# bits2.net
KiCad netlist of a schematic drawn in EAGLE
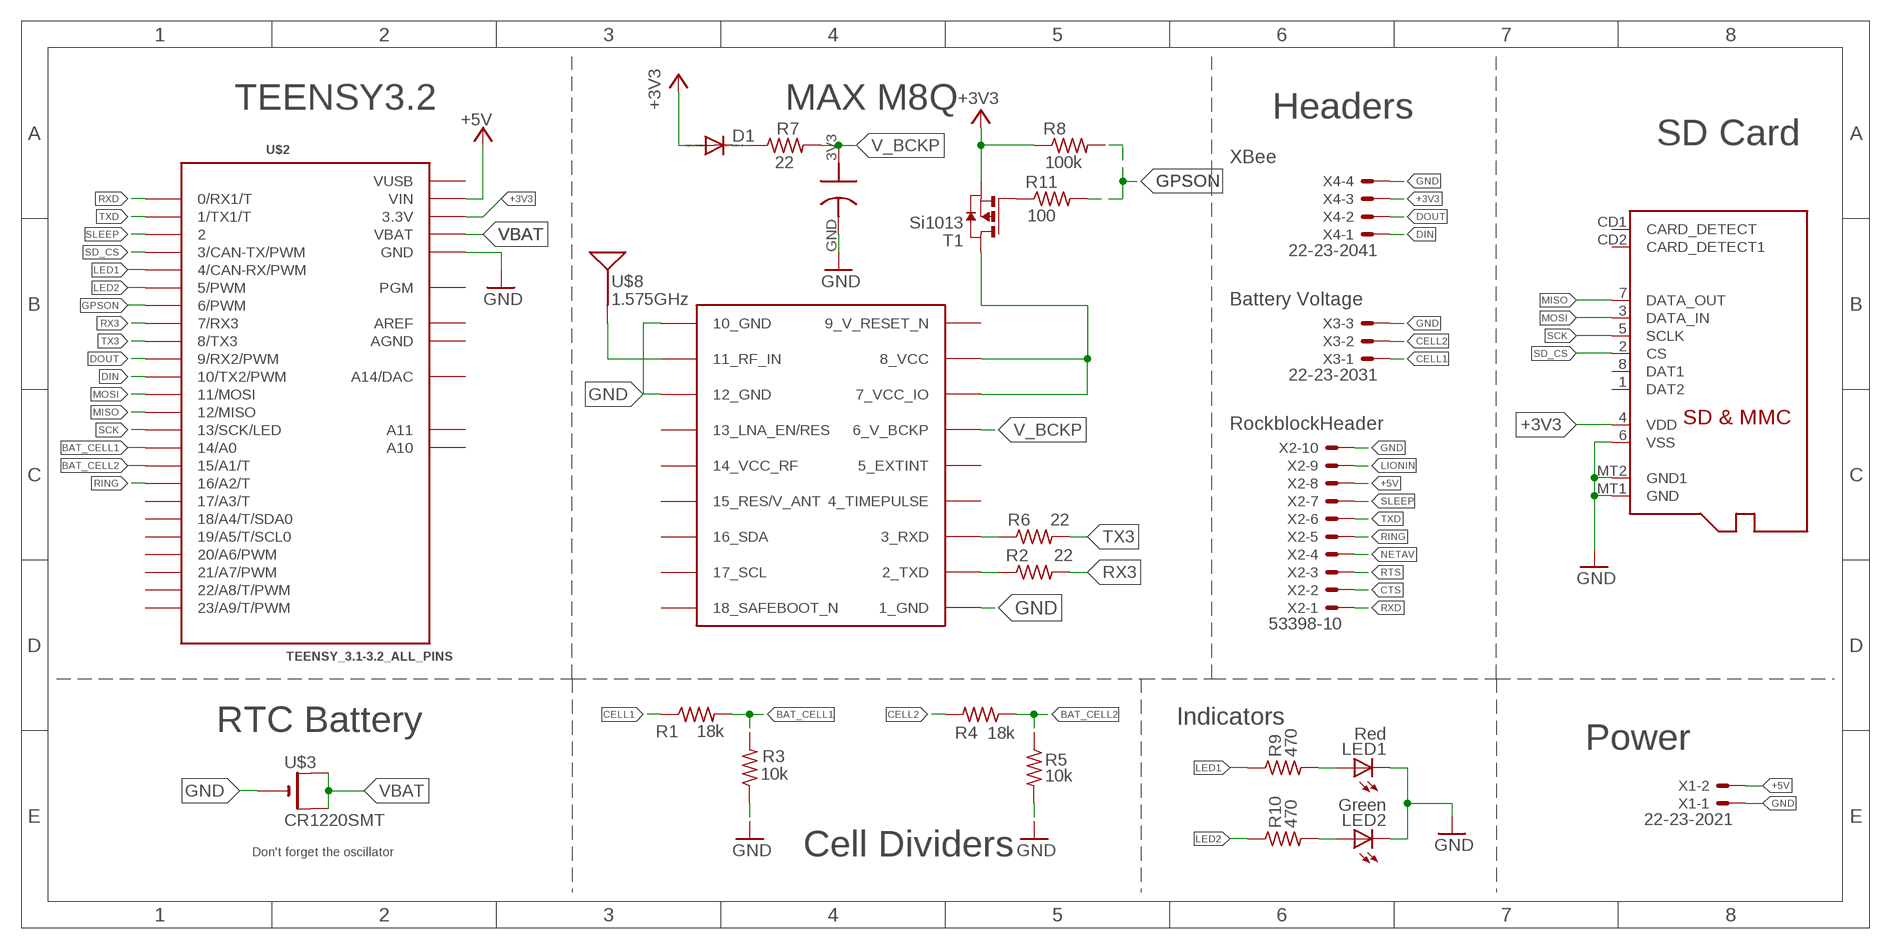
[diagram p0: schematic, sheet 1]

(export (version "E")
  (design (tool "Eeschema 10.0.6"))
  (components
    (comp (ref "C1")
      (value "DCK-3R3E204T614-E")
      (footprint "eagle-import:ELNASUPERCAP")
      (libsource (lib "eagle-import") (part "DCK-3R3E204T614-E"))
    )
    (comp (ref "D1")
      (value "DIODE-SOD523")
      (footprint "eagle-import:SOD523")
      (libsource (lib "eagle-import") (part "DIODE-SOD523"))
    )
    (comp (ref "LED1")
      (value "Red")
      (footprint "eagle-import:CHIP-LED0603")
      (libsource (lib "eagle-import") (part "LEDCHIP-LED0603"))
    )
    (comp (ref "LED2")
      (value "Green")
      (footprint "eagle-import:CHIP-LED0603")
      (libsource (lib "eagle-import") (part "LEDCHIP-LED0603"))
    )
    (comp (ref "R1")
      (value "18k")
      (footprint "eagle-import:R0603")
      (libsource (lib "eagle-import") (part "resistor_348_R-US_R0603"))
    )
    (comp (ref "R2")
      (value "22")
      (footprint "eagle-import:R0603")
      (libsource (lib "eagle-import") (part "R-US_R0603"))
    )
    (comp (ref "R3")
      (value "10k")
      (footprint "eagle-import:R0603")
      (libsource (lib "eagle-import") (part "resistor_348_R-US_R0603"))
    )
    (comp (ref "R4")
      (value "18k")
      (footprint "eagle-import:R0603")
      (libsource (lib "eagle-import") (part "resistor_348_R-US_R0603"))
    )
    (comp (ref "R5")
      (value "10k")
      (footprint "eagle-import:R0603")
      (libsource (lib "eagle-import") (part "resistor_348_R-US_R0603"))
    )
    (comp (ref "R6")
      (value "22")
      (footprint "eagle-import:R0603")
      (libsource (lib "eagle-import") (part "R-US_R0603"))
    )
    (comp (ref "R7")
      (value "22")
      (footprint "eagle-import:R0603")
      (libsource (lib "eagle-import") (part "R-US_R0603"))
    )
    (comp (ref "R8")
      (value "100k")
      (footprint "eagle-import:R0603")
      (libsource (lib "eagle-import") (part "R-US_R0603"))
    )
    (comp (ref "R9")
      (value "470")
      (footprint "eagle-import:R0603")
      (libsource (lib "eagle-import") (part "resistor_348_R-US_R0603"))
    )
    (comp (ref "R10")
      (value "470")
      (footprint "eagle-import:R0603")
      (libsource (lib "eagle-import") (part "resistor_348_R-US_R0603"))
    )
    (comp (ref "R11")
      (value "100")
      (footprint "eagle-import:R0603")
      (libsource (lib "eagle-import") (part "R-US_R0603"))
    )
    (comp (ref "T1")
      (value "Si1013")
      (footprint "eagle-import:SOT-23")
      (fields (field (name "SPICEPREFIX") "J"))
      (libsource (lib "eagle-import") (part "PMOSSOT23"))
    )
    (comp (ref "U$1")
      (value "MICROSD")
      (footprint "eagle-import:MICROSD")
      (libsource (lib "eagle-import") (part "MICROSD"))
    )
    (comp (ref "U$2")
      (value "TEENSY_3.1-3.2_ALL_PINS")
      (footprint "eagle-import:TEENSY_3.0-3.2&LC_ALL_PINS")
      (libsource (lib "eagle-import") (part "TEENSY_3.1-3.2_ALL_PINS"))
    )
    (comp (ref "U$3")
      (value "CR1220SMT")
      (footprint "eagle-import:CR1220-SMD")
      (libsource (lib "eagle-import") (part "CR1220SMT"))
    )
    (comp (ref "U$7")
      (value "MAX-M8")
      (footprint "eagle-import:MAX-M8")
      (libsource (lib "eagle-import") (part "MAX-M8"))
    )
    (comp (ref "U$8")
      (value "1.575GHz")
      (footprint "eagle-import:SPARKFUN-GPS_ANT-GPS-2X7MM")
      (libsource (lib "eagle-import") (part "SPARKFUN-GPS_ANTENNAGPS-2X7MM"))
    )
    (comp (ref "X1")
      (value "22-23-2021")
      (footprint "eagle-import:22-23-2021")
      (fields (field (name "MF") "MOLEX"))
      (libsource (lib "eagle-import") (part "22-23-2021"))
    )
    (comp (ref "X2")
      (value "53398-10")
      (footprint "eagle-import:53398-10")
      (fields (field (name "MF") "MOLEX") (field (name "MPN") "53398-1071"))
      (libsource (lib "eagle-import") (part "53?-10398"))
    )
    (comp (ref "X3")
      (value "22-23-2031")
      (footprint "eagle-import:22-23-2031")
      (fields (field (name "MF") "MOLEX"))
      (libsource (lib "eagle-import") (part "22-23-2031"))
    )
    (comp (ref "X4")
      (value "22-23-2041")
      (footprint "eagle-import:22-23-2041")
      (fields (field (name "MF") "MOLEX"))
      (libsource (lib "eagle-import") (part "22-23-2041"))
    )
  )
  (nets
    (net (code "1") (name "+3V3") (class "Default")
      (node (ref "D1") (pin "A") (pinfunction "A_A") (pintype "passive"))
      (node (ref "R8") (pin "1") (pinfunction "1_1") (pintype "passive"))
      (node (ref "T1") (pin "2") (pinfunction "S_2") (pintype "passive"))
      (node (ref "U$1") (pin "4") (pinfunction "VDD_4") (pintype "power_in"))
      (node (ref "U$2") (pin "3.3V") (pinfunction "3.3V_3.3V") (pintype "power_in"))
      (node (ref "U$2") (pin "3.3V1") (pinfunction "3.3V_3.3V1") (pintype "power_in"))
      (node (ref "X4") (pin "3") (pinfunction "S_3") (pintype "passive"))
    )
    (net (code "2") (name "+5V") (class "Default")
      (node (ref "U$2") (pin "VIN") (pinfunction "VIN_VIN") (pintype "power_in"))
      (node (ref "X1") (pin "2") (pinfunction "S_2") (pintype "passive"))
      (node (ref "X2") (pin "8") (pinfunction "S_8") (pintype "passive"))
    )
    (net (code "3") (name "/9_V_RESET_N") (class "Default")
      (node (ref "U$7") (pin "9_RESET_N") (pinfunction "9_V_RESET_N_9_RESET_N") (pintype "power_in"))
    )
    (net (code "4") (name "/AGND") (class "Default")
      (node (ref "U$2") (pin "AGND") (pinfunction "AGND_AGND") (pintype "power_in"))
    )
    (net (code "5") (name "/AREF") (class "Default")
      (node (ref "U$2") (pin "AREF") (pinfunction "AREF_AREF") (pintype "power_in"))
    )
    (net (code "6") (name "/VUSB") (class "Default")
      (node (ref "U$2") (pin "VUSB") (pinfunction "VUSB_VUSB") (pintype "power_in"))
    )
    (net (code "7") (name "BAT_CELL1") (class "Default")
      (node (ref "R1") (pin "2") (pinfunction "2_2") (pintype "passive"))
      (node (ref "R3") (pin "2") (pinfunction "2_2") (pintype "passive"))
      (node (ref "U$2") (pin "14/A0") (pinfunction "14/A0_14/A0") (pintype "bidirectional"))
    )
    (net (code "8") (name "BAT_CELL2") (class "Default")
      (node (ref "R4") (pin "1") (pinfunction "1_1") (pintype "passive"))
      (node (ref "R5") (pin "1") (pinfunction "1_1") (pintype "passive"))
      (node (ref "U$2") (pin "15/A1") (pinfunction "15/A1/T_15/A1") (pintype "bidirectional"))
    )
    (net (code "9") (name "CELL1") (class "Default")
      (node (ref "R1") (pin "1") (pinfunction "1_1") (pintype "passive"))
      (node (ref "X3") (pin "1") (pinfunction "S_1") (pintype "passive"))
    )
    (net (code "10") (name "CELL2") (class "Default")
      (node (ref "R4") (pin "2") (pinfunction "2_2") (pintype "passive"))
      (node (ref "X3") (pin "2") (pinfunction "S_2") (pintype "passive"))
    )
    (net (code "11") (name "CTS") (class "Default")
      (node (ref "X2") (pin "2") (pinfunction "S_2") (pintype "passive"))
    )
    (net (code "12") (name "DIN") (class "Default")
      (node (ref "U$2") (pin "10") (pinfunction "10/TX2/PWM_10") (pintype "bidirectional"))
      (node (ref "X4") (pin "1") (pinfunction "S_1") (pintype "passive"))
    )
    (net (code "13") (name "DOUT") (class "Default")
      (node (ref "U$2") (pin "9") (pinfunction "9/RX2/PWM_9") (pintype "bidirectional"))
      (node (ref "X4") (pin "2") (pinfunction "S_2") (pintype "passive"))
    )
    (net (code "14") (name "GND") (class "Default")
      (node (ref "C1") (pin "GND") (pinfunction "GND_GND") (pintype "bidirectional"))
      (node (ref "LED1") (pin "C") (pinfunction "C_C") (pintype "passive"))
      (node (ref "LED2") (pin "C") (pinfunction "C_C") (pintype "passive"))
      (node (ref "R3") (pin "1") (pinfunction "1_1") (pintype "passive"))
      (node (ref "R5") (pin "2") (pinfunction "2_2") (pintype "passive"))
      (node (ref "U$1") (pin "6") (pinfunction "VSS_6") (pintype "power_in"))
      (node (ref "U$1") (pin "MT1") (pinfunction "GND_MT1") (pintype "power_in"))
      (node (ref "U$1") (pin "MT2") (pinfunction "GND1_MT2") (pintype "power_in"))
      (node (ref "U$2") (pin "GND") (pinfunction "GND_GND") (pintype "power_in"))
      (node (ref "U$2") (pin "GND1") (pinfunction "GND_GND1") (pintype "power_in"))
      (node (ref "U$3") (pin "-") (pinfunction "-_-") (pintype "passive"))
      (node (ref "U$7") (pin "10_GND") (pinfunction "10_GND_10_GND") (pintype "power_in"))
      (node (ref "U$7") (pin "12_GND") (pinfunction "12_GND_12_GND") (pintype "power_in"))
      (node (ref "U$7") (pin "1_GND") (pinfunction "1_GND_1_GND") (pintype "power_in"))
      (node (ref "X1") (pin "1") (pinfunction "S_1") (pintype "passive"))
      (node (ref "X2") (pin "10") (pinfunction "S_10") (pintype "passive"))
      (node (ref "X3") (pin "3") (pinfunction "S_3") (pintype "passive"))
      (node (ref "X4") (pin "4") (pinfunction "S_4") (pintype "passive"))
    )
    (net (code "15") (name "GPSON") (class "Default")
      (node (ref "R11") (pin "2") (pinfunction "2_2") (pintype "passive"))
      (node (ref "R8") (pin "2") (pinfunction "2_2") (pintype "passive"))
      (node (ref "U$2") (pin "6") (pinfunction "6/PWM_6") (pintype "bidirectional"))
    )
    (net (code "16") (name "LED1") (class "Default")
      (node (ref "R9") (pin "1") (pinfunction "1_1") (pintype "passive"))
      (node (ref "U$2") (pin "4") (pinfunction "4/CAN-RX/PWM_4") (pintype "bidirectional"))
    )
    (net (code "17") (name "LED2") (class "Default")
      (node (ref "R10") (pin "1") (pinfunction "1_1") (pintype "passive"))
      (node (ref "U$2") (pin "5") (pinfunction "5/PWM_5") (pintype "bidirectional"))
    )
    (net (code "18") (name "LIONIN") (class "Default")
      (node (ref "X2") (pin "9") (pinfunction "S_9") (pintype "passive"))
    )
    (net (code "19") (name "MISO") (class "Default")
      (node (ref "U$1") (pin "7") (pinfunction "DATA_OUT_7") (pintype "output"))
      (node (ref "U$2") (pin "12") (pinfunction "12/MISO_12") (pintype "bidirectional"))
    )
    (net (code "20") (name "MOSI") (class "Default")
      (node (ref "U$1") (pin "3") (pinfunction "DATA_IN_3") (pintype "input"))
      (node (ref "U$2") (pin "11") (pinfunction "11/MOSI_11") (pintype "bidirectional"))
    )
    (net (code "21") (name "NETAV") (class "Default")
      (node (ref "X2") (pin "4") (pinfunction "S_4") (pintype "passive"))
    )
    (net (code "22") (name "Net-(D1-PadC)") (class "Default")
      (node (ref "D1") (pin "C") (pinfunction "C_C") (pintype "passive"))
      (node (ref "R7") (pin "1") (pinfunction "1_1") (pintype "passive"))
    )
    (net (code "23") (name "Net-(LED1-PadA)") (class "Default")
      (node (ref "LED1") (pin "A") (pinfunction "A_A") (pintype "passive"))
      (node (ref "R9") (pin "2") (pinfunction "2_2") (pintype "passive"))
    )
    (net (code "24") (name "Net-(LED2-PadA)") (class "Default")
      (node (ref "LED2") (pin "A") (pinfunction "A_A") (pintype "passive"))
      (node (ref "R10") (pin "2") (pinfunction "2_2") (pintype "passive"))
    )
    (net (code "25") (name "Net-(R2-Pad1)") (class "Default")
      (node (ref "R2") (pin "1") (pinfunction "1_1") (pintype "passive"))
      (node (ref "U$7") (pin "2_TXD") (pinfunction "2_TXD_2_TXD") (pintype "bidirectional"))
    )
    (net (code "26") (name "Net-(R6-Pad1)") (class "Default")
      (node (ref "R6") (pin "1") (pinfunction "1_1") (pintype "passive"))
      (node (ref "U$7") (pin "3_RXD") (pinfunction "3_RXD_3_RXD") (pintype "bidirectional"))
    )
    (net (code "27") (name "Net-(T1-D)") (class "Default")
      (node (ref "T1") (pin "1") (pinfunction "D_1") (pintype "passive"))
      (node (ref "U$7") (pin "7_VCC_IO") (pinfunction "7_VCC_IO_7_VCC_IO") (pintype "power_in"))
      (node (ref "U$7") (pin "8_VCC") (pinfunction "8_VCC_8_VCC") (pintype "power_in"))
    )
    (net (code "28") (name "Net-(T1-G)") (class "Default")
      (node (ref "R11") (pin "1") (pinfunction "1_1") (pintype "passive"))
      (node (ref "T1") (pin "3") (pinfunction "G_3") (pintype "passive"))
    )
    (net (code "29") (name "Net-(U$8-SIGNAL)") (class "Default")
      (node (ref "U$7") (pin "11_RF_IN") (pinfunction "11_RF_IN_11_RF_IN") (pintype "bidirectional"))
      (node (ref "U$8") (pin "1") (pinfunction "SIGNAL_1") (pintype "bidirectional"))
    )
    (net (code "30") (name "RING") (class "Default")
      (node (ref "U$2") (pin "16/A2") (pinfunction "16/A2/T_16/A2") (pintype "bidirectional"))
      (node (ref "X2") (pin "5") (pinfunction "S_5") (pintype "passive"))
    )
    (net (code "31") (name "RTS") (class "Default")
      (node (ref "X2") (pin "3") (pinfunction "S_3") (pintype "passive"))
    )
    (net (code "32") (name "RX3") (class "Default")
      (node (ref "R2") (pin "2") (pinfunction "2_2") (pintype "passive"))
      (node (ref "U$2") (pin "7") (pinfunction "7/RX3_7") (pintype "bidirectional"))
    )
    (net (code "33") (name "RXD") (class "Default")
      (node (ref "U$2") (pin "0") (pinfunction "0/RX1/T_0") (pintype "bidirectional"))
      (node (ref "X2") (pin "1") (pinfunction "S_1") (pintype "passive"))
    )
    (net (code "34") (name "SCK") (class "Default")
      (node (ref "U$1") (pin "5") (pinfunction "SCLK_5") (pintype "input"))
      (node (ref "U$2") (pin "13") (pinfunction "13/SCK/LED_13") (pintype "bidirectional"))
    )
    (net (code "35") (name "SD_CS") (class "Default")
      (node (ref "U$1") (pin "2") (pinfunction "CS_2") (pintype "input"))
      (node (ref "U$2") (pin "3") (pinfunction "3/CAN-TX/PWM_3") (pintype "bidirectional"))
    )
    (net (code "36") (name "SLEEP") (class "Default")
      (node (ref "U$2") (pin "2") (pinfunction "2_2") (pintype "bidirectional"))
      (node (ref "X2") (pin "7") (pinfunction "S_7") (pintype "passive"))
    )
    (net (code "37") (name "TX3") (class "Default")
      (node (ref "R6") (pin "2") (pinfunction "2_2") (pintype "passive"))
      (node (ref "U$2") (pin "8") (pinfunction "8/TX3_8") (pintype "bidirectional"))
    )
    (net (code "38") (name "TXD") (class "Default")
      (node (ref "U$2") (pin "1") (pinfunction "1/TX1/T_1") (pintype "bidirectional"))
      (node (ref "X2") (pin "6") (pinfunction "S_6") (pintype "passive"))
    )
    (net (code "39") (name "VBAT") (class "Default")
      (node (ref "U$2") (pin "VBAT") (pinfunction "VBAT_VBAT") (pintype "power_in"))
      (node (ref "U$3") (pin "+$1") (pinfunction "+_+$1") (pintype "passive"))
      (node (ref "U$3") (pin "+$2") (pinfunction "+1_+$2") (pintype "passive"))
    )
    (net (code "40") (name "V_BCKP") (class "Default")
      (node (ref "C1") (pin "3V3") (pinfunction "3V3_3V3") (pintype "bidirectional"))
      (node (ref "R7") (pin "2") (pinfunction "2_2") (pintype "passive"))
      (node (ref "U$7") (pin "6_V_BCKP") (pinfunction "6_V_BCKP_6_V_BCKP") (pintype "bidirectional"))
    )
    (net (code "41") (name "unconnected-(U$1-CARD_DETECT-PadCD1)") (class "Default")
      (node (ref "U$1") (pin "CD1") (pinfunction "CARD_DETECT_CD1") (pintype "passive"))
    )
    (net (code "42") (name "unconnected-(U$1-CARD_DETECT1-PadCD2)") (class "Default")
      (node (ref "U$1") (pin "CD2") (pinfunction "CARD_DETECT1_CD2") (pintype "passive"))
    )
    (net (code "43") (name "unconnected-(U$1-DAT1-Pad8)") (class "Default")
      (node (ref "U$1") (pin "8") (pinfunction "DAT1_8") (pintype "bidirectional"))
    )
    (net (code "44") (name "unconnected-(U$1-DAT2-Pad1)") (class "Default")
      (node (ref "U$1") (pin "1") (pinfunction "DAT2_1") (pintype "bidirectional"))
    )
    (net (code "45") (name "unconnected-(U$2-17{slash}A3{slash}T-Pad17{slash}A3)") (class "Default")
      (node (ref "U$2") (pin "17/A3") (pinfunction "17/A3/T_17/A3") (pintype "bidirectional"))
    )
    (net (code "46") (name "unconnected-(U$2-18{slash}A4{slash}T{slash}SDA0-Pad18{slash}A4)") (class "Default")
      (node (ref "U$2") (pin "18/A4") (pinfunction "18/A4/T/SDA0_18/A4") (pintype "bidirectional"))
    )
    (net (code "47") (name "unconnected-(U$2-19{slash}A5{slash}T{slash}SCL0-Pad19{slash}A5)") (class "Default")
      (node (ref "U$2") (pin "19/A5") (pinfunction "19/A5/T/SCL0_19/A5") (pintype "bidirectional"))
    )
    (net (code "48") (name "unconnected-(U$2-20{slash}A6{slash}PWM-Pad20{slash}A6)") (class "Default")
      (node (ref "U$2") (pin "20/A6") (pinfunction "20/A6/PWM_20/A6") (pintype "bidirectional"))
    )
    (net (code "49") (name "unconnected-(U$2-21{slash}A7{slash}PWM-Pad21{slash}A7)") (class "Default")
      (node (ref "U$2") (pin "21/A7") (pinfunction "21/A7/PWM_21/A7") (pintype "bidirectional"))
    )
    (net (code "50") (name "unconnected-(U$2-22{slash}A8{slash}T{slash}PWM-Pad22{slash}A8)") (class "Default")
      (node (ref "U$2") (pin "22/A8") (pinfunction "22/A8/T/PWM_22/A8") (pintype "bidirectional"))
    )
    (net (code "51") (name "unconnected-(U$2-23{slash}A9{slash}T{slash}PWM-Pad23{slash}A9)") (class "Default")
      (node (ref "U$2") (pin "23/A9") (pinfunction "23/A9/T/PWM_23/A9") (pintype "bidirectional"))
    )
    (net (code "52") (name "unconnected-(U$2-A14{slash}DAC-PadRESET{slash}DAC)") (class "Default")
      (node (ref "U$2") (pin "RESET/DAC") (pinfunction "A14/DAC_RESET/DAC") (pintype "bidirectional"))
    )
    (net (code "53") (name "unconnected-(U$2-PadA10)") (class "Default")
      (node (ref "U$2") (pin "A10") (pinfunction "A10_A10") (pintype "bidirectional"))
    )
    (net (code "54") (name "unconnected-(U$2-PadA11)") (class "Default")
      (node (ref "U$2") (pin "A11") (pinfunction "A11_A11") (pintype "bidirectional"))
    )
    (net (code "55") (name "unconnected-(U$2-PadPGM)") (class "Default")
      (node (ref "U$2") (pin "PGM") (pinfunction "PGM_PGM") (pintype "bidirectional"))
    )
    (net (code "56") (name "unconnected-(U$7-13_LNA_EN{slash}RES-Pad13_LNA_EN)") (class "Default")
      (node (ref "U$7") (pin "13_LNA_EN") (pinfunction "13_LNA_EN/RES_13_LNA_EN") (pintype "bidirectional"))
    )
    (net (code "57") (name "unconnected-(U$7-15_RES{slash}V_ANT-Pad15_V_ANT{slash}RESERVED)") (class "Default")
      (node (ref "U$7") (pin "15_V_ANT/RESERVED") (pinfunction "15_RES/V_ANT_15_V_ANT/RESERVED") (pintype "bidirectional"))
    )
    (net (code "58") (name "unconnected-(U$7-Pad4_TIMEPULSE)") (class "Default")
      (node (ref "U$7") (pin "4_TIMEPULSE") (pinfunction "4_TIMEPULSE_4_TIMEPULSE") (pintype "bidirectional"))
    )
    (net (code "59") (name "unconnected-(U$7-Pad5_EXTINT)") (class "Default")
      (node (ref "U$7") (pin "5_EXTINT") (pinfunction "5_EXTINT_5_EXTINT") (pintype "bidirectional"))
    )
    (net (code "60") (name "unconnected-(U$7-Pad14_VCC_RF)") (class "Default")
      (node (ref "U$7") (pin "14_VCC_RF") (pinfunction "14_VCC_RF_14_VCC_RF") (pintype "bidirectional"))
    )
    (net (code "61") (name "unconnected-(U$7-Pad16_SDA)") (class "Default")
      (node (ref "U$7") (pin "16_SDA") (pinfunction "16_SDA_16_SDA") (pintype "bidirectional"))
    )
    (net (code "62") (name "unconnected-(U$7-Pad17_SCL)") (class "Default")
      (node (ref "U$7") (pin "17_SCL") (pinfunction "17_SCL_17_SCL") (pintype "bidirectional"))
    )
    (net (code "63") (name "unconnected-(U$7-Pad18_SAFEBOOT_N)") (class "Default")
      (node (ref "U$7") (pin "18_SAFEBOOT_N") (pinfunction "18_SAFEBOOT_N_18_SAFEBOOT_N") (pintype "bidirectional"))
    )
  )
)
